# OpenDTU_USB.net
KiCad netlist of a schematic drawn in EAGLE
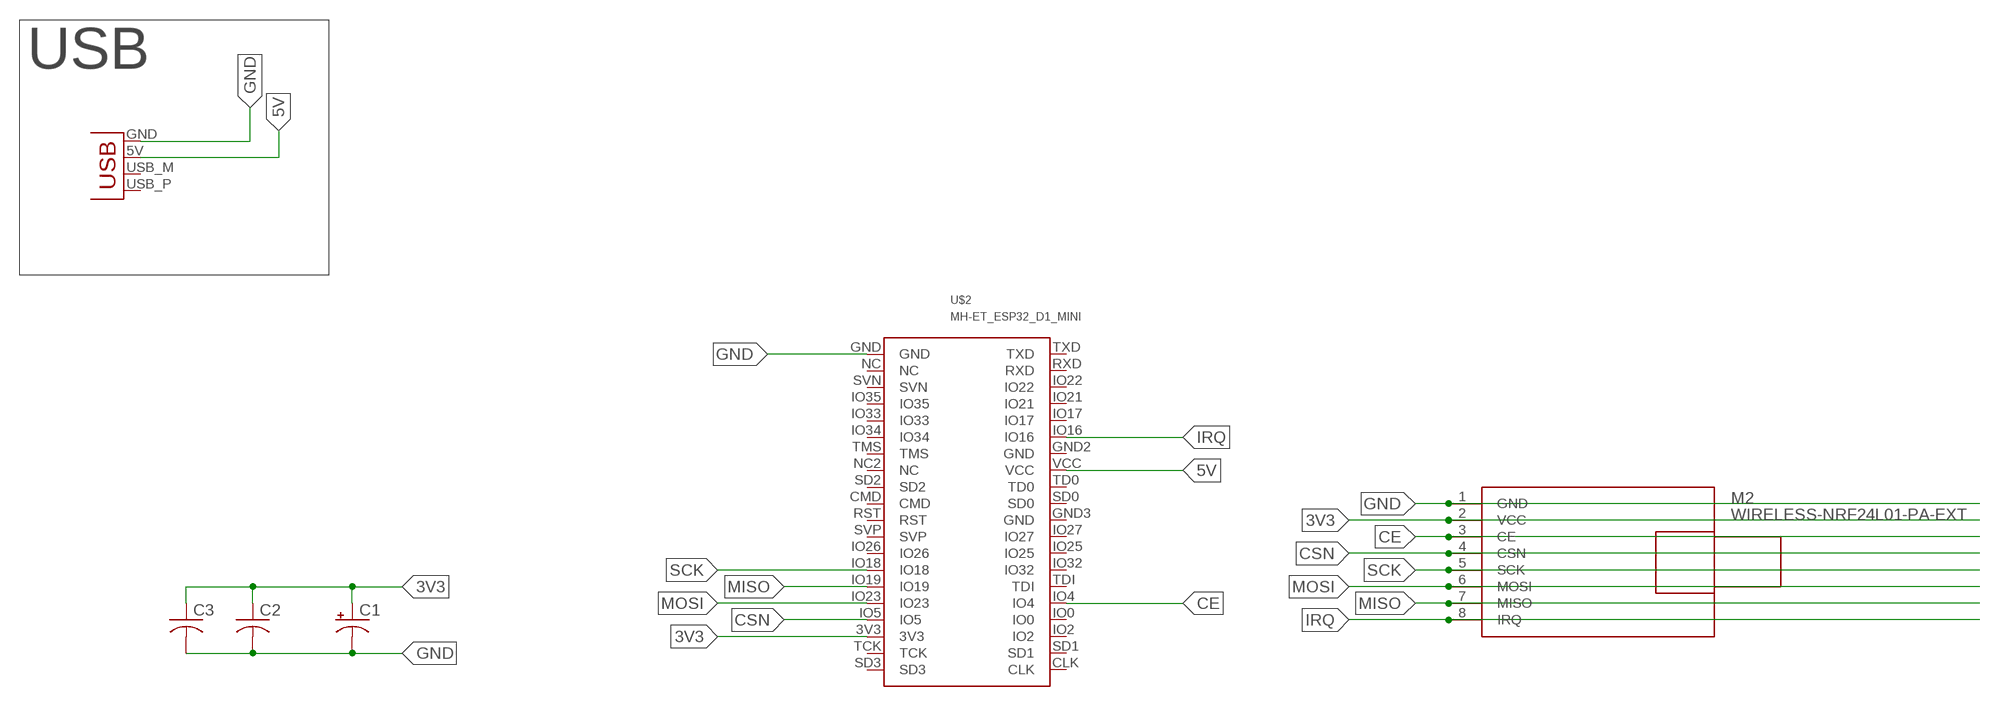
[diagram p0: schematic, sheet 1]

(export (version "E")
  (design (tool "Eeschema 10.0.6"))
  (components
    (comp (ref "C1")
      (value "CPOL-USE2.5-6")
      (footprint "eagle-import:E2,5-6")
      (libsource (lib "eagle-import") (part "CPOL-USE2.5-6"))
    )
    (comp (ref "C2")
      (value "C-USC0805K")
      (footprint "eagle-import:C0805K")
      (libsource (lib "eagle-import") (part "C-USC0805K"))
    )
    (comp (ref "C3")
      (value "C-USC0805K")
      (footprint "eagle-import:C0805K")
      (libsource (lib "eagle-import") (part "C-USC0805K"))
    )
    (comp (ref "M2")
      (value "WIRELESS-NRF24L01-PA-EXT")
      (footprint "eagle-import:WIRELESS-NRF24L01-PA-EXT")
      (libsource (lib "eagle-import") (part "WIRELESS-NRF24L01-PA-EXT"))
    )
    (comp (ref "U$2")
      (value "MH-ET_ESP32_D1_MINI")
      (footprint "eagle-import:MH-ET_ESP32_D1_MINI")
      (libsource (lib "eagle-import") (part "MH-ET_ESP32_D1_MINI"))
    )
    (comp (ref "X1")
      (value "USBPCB")
      (footprint "eagle-import:USB-A-PCB")
      (libsource (lib "eagle-import") (part "USBPCB"))
    )
  )
  (nets
    (net (code "1") (name "3V3") (class "Default")
      (node (ref "C1") (pin "+") (pinfunction "+_+") (pintype "passive"))
      (node (ref "C2") (pin "1") (pinfunction "1_1") (pintype "passive"))
      (node (ref "C3") (pin "1") (pinfunction "1_1") (pintype "passive"))
      (node (ref "M2") (pin "2") (pinfunction "VCC_2") (pintype "power_in"))
      (node (ref "U$2") (pin "3V3") (pinfunction "3V3_3V3") (pintype "bidirectional"))
    )
    (net (code "2") (name "5V") (class "Default")
      (node (ref "U$2") (pin "VCC") (pinfunction "VCC_VCC") (pintype "bidirectional"))
      (node (ref "X1") (pin "5V") (pinfunction "VBUS_5V") (pintype "bidirectional"))
    )
    (net (code "3") (name "CE") (class "Default")
      (node (ref "M2") (pin "3") (pinfunction "CE_3") (pintype "bidirectional"))
      (node (ref "U$2") (pin "IO4") (pinfunction "IO4_IO4") (pintype "bidirectional"))
    )
    (net (code "4") (name "CSN") (class "Default")
      (node (ref "M2") (pin "4") (pinfunction "CSN_4") (pintype "bidirectional"))
      (node (ref "U$2") (pin "IO5") (pinfunction "IO5_IO5") (pintype "bidirectional"))
    )
    (net (code "5") (name "GND") (class "Default")
      (node (ref "C1") (pin "-") (pinfunction "-_-") (pintype "passive"))
      (node (ref "C2") (pin "2") (pinfunction "2_2") (pintype "passive"))
      (node (ref "C3") (pin "2") (pinfunction "2_2") (pintype "passive"))
      (node (ref "M2") (pin "1") (pinfunction "GND_1") (pintype "power_in"))
      (node (ref "U$2") (pin "GND") (pinfunction "GND_GND") (pintype "bidirectional"))
      (node (ref "X1") (pin "GND") (pinfunction "GND_GND") (pintype "bidirectional"))
    )
    (net (code "6") (name "IRQ") (class "Default")
      (node (ref "M2") (pin "8") (pinfunction "IRQ_8") (pintype "bidirectional"))
      (node (ref "U$2") (pin "IO16") (pinfunction "IO16_IO16") (pintype "bidirectional"))
    )
    (net (code "7") (name "MISO") (class "Default")
      (node (ref "M2") (pin "7") (pinfunction "MISO_7") (pintype "bidirectional"))
      (node (ref "U$2") (pin "IO19") (pinfunction "IO19_IO19") (pintype "bidirectional"))
    )
    (net (code "8") (name "MOSI") (class "Default")
      (node (ref "M2") (pin "6") (pinfunction "MOSI_6") (pintype "bidirectional"))
      (node (ref "U$2") (pin "IO23") (pinfunction "IO23_IO23") (pintype "bidirectional"))
    )
    (net (code "9") (name "SCK") (class "Default")
      (node (ref "M2") (pin "5") (pinfunction "SCK_5") (pintype "bidirectional"))
      (node (ref "U$2") (pin "IO18") (pinfunction "IO18_IO18") (pintype "bidirectional"))
    )
    (net (code "10") (name "unconnected-(U$2-GND-PadGND2)") (class "Default")
      (node (ref "U$2") (pin "GND2") (pinfunction "GND_GND2") (pintype "bidirectional"))
    )
    (net (code "11") (name "unconnected-(U$2-GND-PadGND3)") (class "Default")
      (node (ref "U$2") (pin "GND3") (pinfunction "GND_GND3") (pintype "bidirectional"))
    )
    (net (code "12") (name "unconnected-(U$2-NC-PadNC2)") (class "Default")
      (node (ref "U$2") (pin "NC2") (pinfunction "NC_NC2") (pintype "bidirectional"))
    )
    (net (code "13") (name "unconnected-(U$2-PadCLK)") (class "Default")
      (node (ref "U$2") (pin "CLK") (pinfunction "CLK_CLK") (pintype "bidirectional"))
    )
    (net (code "14") (name "unconnected-(U$2-PadCMD)") (class "Default")
      (node (ref "U$2") (pin "CMD") (pinfunction "CMD_CMD") (pintype "bidirectional"))
    )
    (net (code "15") (name "unconnected-(U$2-PadIO0)") (class "Default")
      (node (ref "U$2") (pin "IO0") (pinfunction "IO0_IO0") (pintype "bidirectional"))
    )
    (net (code "16") (name "unconnected-(U$2-PadIO2)") (class "Default")
      (node (ref "U$2") (pin "IO2") (pinfunction "IO2_IO2") (pintype "bidirectional"))
    )
    (net (code "17") (name "unconnected-(U$2-PadIO17)") (class "Default")
      (node (ref "U$2") (pin "IO17") (pinfunction "IO17_IO17") (pintype "bidirectional"))
    )
    (net (code "18") (name "unconnected-(U$2-PadIO21)") (class "Default")
      (node (ref "U$2") (pin "IO21") (pinfunction "IO21_IO21") (pintype "bidirectional"))
    )
    (net (code "19") (name "unconnected-(U$2-PadIO22)") (class "Default")
      (node (ref "U$2") (pin "IO22") (pinfunction "IO22_IO22") (pintype "bidirectional"))
    )
    (net (code "20") (name "unconnected-(U$2-PadIO25)") (class "Default")
      (node (ref "U$2") (pin "IO25") (pinfunction "IO25_IO25") (pintype "bidirectional"))
    )
    (net (code "21") (name "unconnected-(U$2-PadIO26)") (class "Default")
      (node (ref "U$2") (pin "IO26") (pinfunction "IO26_IO26") (pintype "bidirectional"))
    )
    (net (code "22") (name "unconnected-(U$2-PadIO27)") (class "Default")
      (node (ref "U$2") (pin "IO27") (pinfunction "IO27_IO27") (pintype "bidirectional"))
    )
    (net (code "23") (name "unconnected-(U$2-PadIO32)") (class "Default")
      (node (ref "U$2") (pin "IO32") (pinfunction "IO32_IO32") (pintype "bidirectional"))
    )
    (net (code "24") (name "unconnected-(U$2-PadIO33)") (class "Default")
      (node (ref "U$2") (pin "IO33") (pinfunction "IO33_IO33") (pintype "bidirectional"))
    )
    (net (code "25") (name "unconnected-(U$2-PadIO34)") (class "Default")
      (node (ref "U$2") (pin "IO34") (pinfunction "IO34_IO34") (pintype "bidirectional"))
    )
    (net (code "26") (name "unconnected-(U$2-PadIO35)") (class "Default")
      (node (ref "U$2") (pin "IO35") (pinfunction "IO35_IO35") (pintype "bidirectional"))
    )
    (net (code "27") (name "unconnected-(U$2-PadNC)") (class "Default")
      (node (ref "U$2") (pin "NC") (pinfunction "NC_NC") (pintype "bidirectional"))
    )
    (net (code "28") (name "unconnected-(U$2-PadRST)") (class "Default")
      (node (ref "U$2") (pin "RST") (pinfunction "RST_RST") (pintype "bidirectional"))
    )
    (net (code "29") (name "unconnected-(U$2-PadRXD)") (class "Default")
      (node (ref "U$2") (pin "RXD") (pinfunction "RXD_RXD") (pintype "bidirectional"))
    )
    (net (code "30") (name "unconnected-(U$2-PadSD0)") (class "Default")
      (node (ref "U$2") (pin "SD0") (pinfunction "SD0_SD0") (pintype "bidirectional"))
    )
    (net (code "31") (name "unconnected-(U$2-PadSD1)") (class "Default")
      (node (ref "U$2") (pin "SD1") (pinfunction "SD1_SD1") (pintype "bidirectional"))
    )
    (net (code "32") (name "unconnected-(U$2-PadSD2)") (class "Default")
      (node (ref "U$2") (pin "SD2") (pinfunction "SD2_SD2") (pintype "bidirectional"))
    )
    (net (code "33") (name "unconnected-(U$2-PadSD3)") (class "Default")
      (node (ref "U$2") (pin "SD3") (pinfunction "SD3_SD3") (pintype "bidirectional"))
    )
    (net (code "34") (name "unconnected-(U$2-PadSVN)") (class "Default")
      (node (ref "U$2") (pin "SVN") (pinfunction "SVN_SVN") (pintype "bidirectional"))
    )
    (net (code "35") (name "unconnected-(U$2-PadSVP)") (class "Default")
      (node (ref "U$2") (pin "SVP") (pinfunction "SVP_SVP") (pintype "bidirectional"))
    )
    (net (code "36") (name "unconnected-(U$2-PadTCK)") (class "Default")
      (node (ref "U$2") (pin "TCK") (pinfunction "TCK_TCK") (pintype "bidirectional"))
    )
    (net (code "37") (name "unconnected-(U$2-PadTD0)") (class "Default")
      (node (ref "U$2") (pin "TD0") (pinfunction "TD0_TD0") (pintype "bidirectional"))
    )
    (net (code "38") (name "unconnected-(U$2-PadTDI)") (class "Default")
      (node (ref "U$2") (pin "TDI") (pinfunction "TDI_TDI") (pintype "bidirectional"))
    )
    (net (code "39") (name "unconnected-(U$2-PadTMS)") (class "Default")
      (node (ref "U$2") (pin "TMS") (pinfunction "TMS_TMS") (pintype "bidirectional"))
    )
    (net (code "40") (name "unconnected-(U$2-PadTXD)") (class "Default")
      (node (ref "U$2") (pin "TXD") (pinfunction "TXD_TXD") (pintype "bidirectional"))
    )
    (net (code "41") (name "unconnected-(X1-D+-PadUSB_P)") (class "Default")
      (node (ref "X1") (pin "USB_P") (pinfunction "D+_USB_P") (pintype "bidirectional"))
    )
    (net (code "42") (name "unconnected-(X1-D--PadUSB_M)") (class "Default")
      (node (ref "X1") (pin "USB_M") (pinfunction "D-_USB_M") (pintype "bidirectional"))
    )
  )
)
